# LickStick_v1_0_1.net
KiCad netlist of a schematic drawn in EAGLE
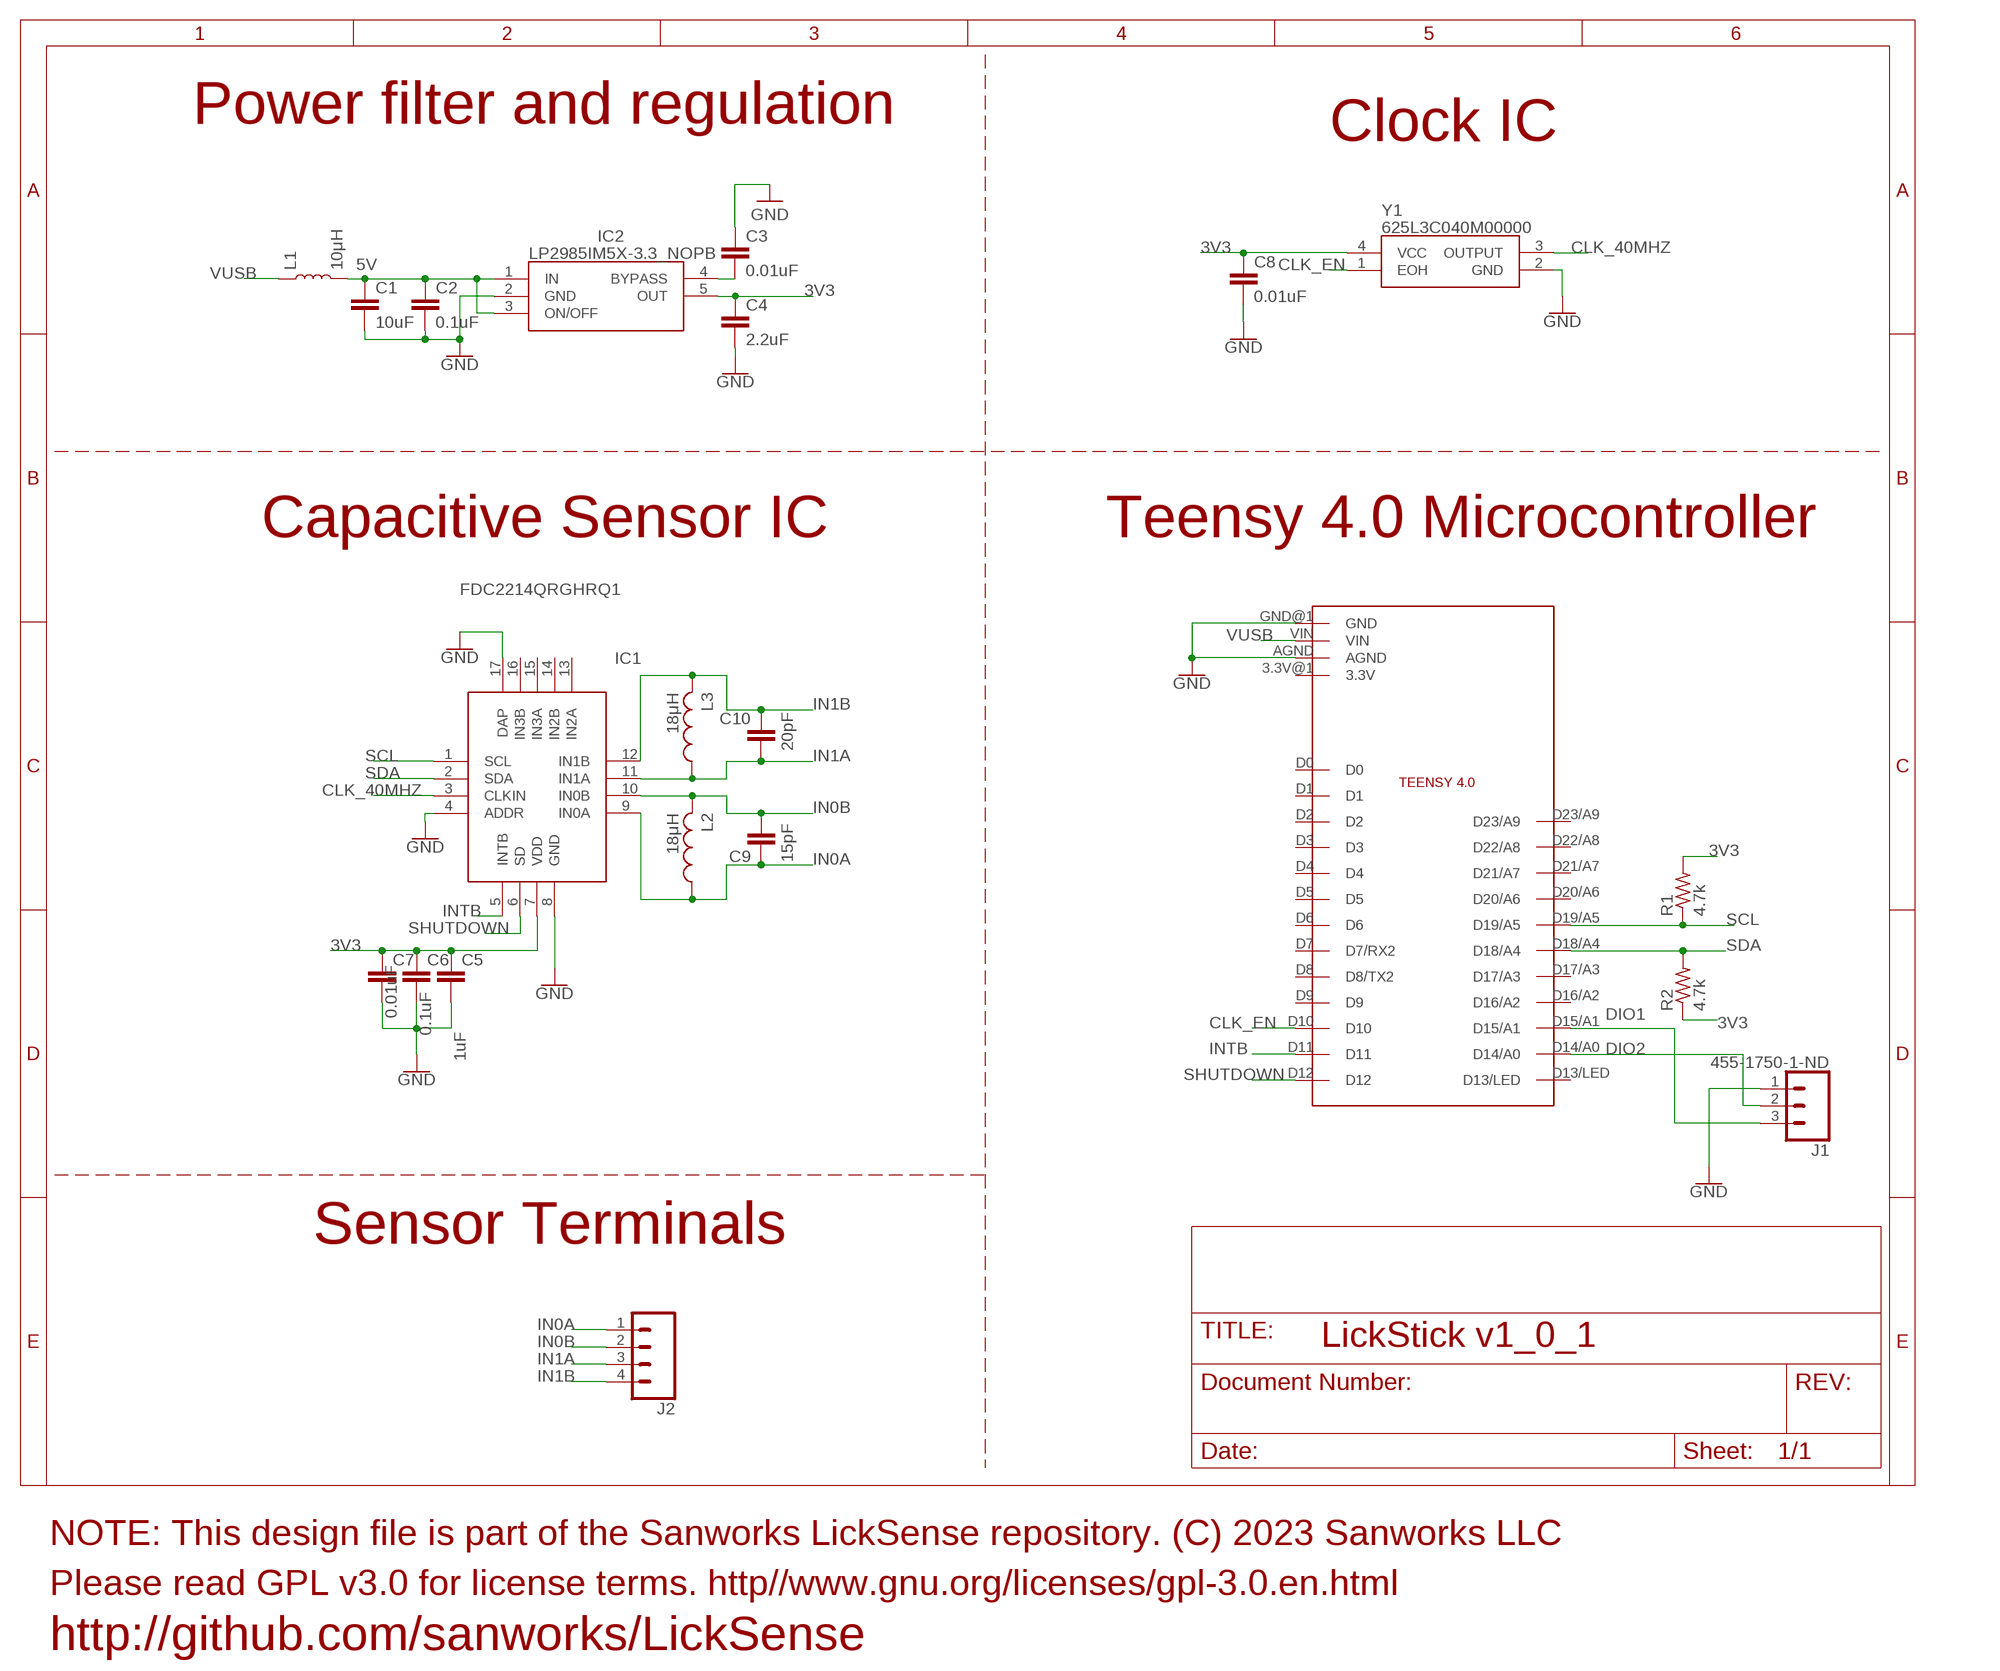
[diagram p0: schematic, sheet 1]

(export (version "E")
  (design (tool "Eeschema 10.0.6"))
  (components
    (comp (ref "C1")
      (value "10uF")
      (footprint "eagle-import:0805")
      (libsource (lib "eagle-import") (part "10UF-0805-10V-10%"))
    )
    (comp (ref "C2")
      (value "0.1uF")
      (footprint "eagle-import:0805")
      (libsource (lib "eagle-import") (part "1.0UF-0805-25V-(+80/-20%)"))
    )
    (comp (ref "C3")
      (value "0.01uF")
      (footprint "eagle-import:0805")
      (libsource (lib "eagle-import") (part "1.0UF-0805-25V-(+80/-20%)"))
    )
    (comp (ref "C4")
      (value "2.2uF")
      (footprint "eagle-import:0805")
      (libsource (lib "eagle-import") (part "1.0UF-0805-25V-(+80/-20%)"))
    )
    (comp (ref "C5")
      (value "1uF")
      (footprint "eagle-import:0805")
      (libsource (lib "eagle-import") (part "1.0UF-0805-25V-(+80/-20%)"))
    )
    (comp (ref "C6")
      (value "0.1uF")
      (footprint "eagle-import:0805")
      (libsource (lib "eagle-import") (part "1.0UF-0805-25V-(+80/-20%)"))
    )
    (comp (ref "C7")
      (value "0.01uF")
      (footprint "eagle-import:0805")
      (libsource (lib "eagle-import") (part "1.0UF-0805-25V-(+80/-20%)"))
    )
    (comp (ref "C8")
      (value "0.01uF")
      (footprint "eagle-import:0805")
      (libsource (lib "eagle-import") (part "1.0UF-0805-25V-(+80/-20%)"))
    )
    (comp (ref "C9")
      (value "15pF")
      (footprint "eagle-import:0805")
      (libsource (lib "eagle-import") (part "1.0UF-0805-25V-(+80/-20%)"))
    )
    (comp (ref "C10")
      (value "20pF")
      (footprint "eagle-import:0805")
      (libsource (lib "eagle-import") (part "1.0UF-0805-25V-(+80/-20%)"))
    )
    (comp (ref "IC1")
      (value "FDC2214QRGHRQ1")
      (footprint "eagle-import:QFN50P400X400X80-17N")
      (fields (field (name "MOUSER_PART_NUMBER") "595-FDC2214QRGHRQ1"))
      (libsource (lib "eagle-import") (part "FDC2214QRGHRQ1"))
    )
    (comp (ref "IC2")
      (value "LP2985IM5X-3.3_NOPB")
      (footprint "eagle-import:SOT95P280X145-5N")
      (fields
        (field (name "MANUFACTURER_PART_NUMBER") "LP2985IM5X-3.3/NOPB")
        (field (name "MOUSER_PART_NUMBER") "926-LP2985IM5X33NOPB")
      )
      (libsource (lib "eagle-import") (part "LP2985IM5X-3.3_NOPB"))
    )
    (comp (ref "J1")
      (value "455-1750-1-ND")
      (footprint "eagle-import:1X03")
      (libsource (lib "eagle-import") (part "CONN_03"))
    )
    (comp (ref "J2")
      (value "CONN_04PTH")
      (footprint "eagle-import:1X04")
      (libsource (lib "eagle-import") (part "CONN_04PTH"))
    )
    (comp (ref "L1")
      (value "10μH")
      (footprint "eagle-import:0806")
      (libsource (lib "eagle-import") (part "2.2μH_SHIELDED_INDUCTOR"))
    )
    (comp (ref "L2")
      (value "18μH")
      (footprint "eagle-import:L3225P")
      (libsource (lib "eagle-import") (part "L-USL3225P"))
    )
    (comp (ref "L3")
      (value "18μH")
      (footprint "eagle-import:L3225P")
      (libsource (lib "eagle-import") (part "L-USL3225P"))
    )
    (comp (ref "MC1")
      (value "TEENSY4.0_SIMPLE_NO_VUSB")
      (footprint "eagle-import:TEENSY4.0_SIMPLE_NO_VUSB")
      (libsource (lib "eagle-import") (part "TEENSY4.0_SIMPLE_NO_VUSB"))
    )
    (comp (ref "R1")
      (value "4.7k")
      (footprint "eagle-import:R0805")
      (libsource (lib "eagle-import") (part "R-US_R0805"))
    )
    (comp (ref "R2")
      (value "4.7k")
      (footprint "eagle-import:R0805")
      (libsource (lib "eagle-import") (part "R-US_R0805"))
    )
    (comp (ref "Y1")
      (value "625L3C040M00000")
      (footprint "eagle-import:625L3C040M00000")
      (fields (field (name "MOUSER_PART_NUMBER") "774-625L3C040M00000"))
      (libsource (lib "eagle-import") (part "625L3C040M00000"))
    )
  )
  (nets
    (net (code "1") (name "/3V3") (class "Default")
      (node (ref "C4") (pin "1") (pinfunction "1_1") (pintype "passive"))
      (node (ref "C5") (pin "1") (pinfunction "1_1") (pintype "passive"))
      (node (ref "C6") (pin "1") (pinfunction "1_1") (pintype "passive"))
      (node (ref "C7") (pin "1") (pinfunction "1_1") (pintype "passive"))
      (node (ref "C8") (pin "1") (pinfunction "1_1") (pintype "passive"))
      (node (ref "IC1") (pin "7") (pinfunction "VDD_7") (pintype "bidirectional"))
      (node (ref "IC2") (pin "5") (pinfunction "OUT_5") (pintype "bidirectional"))
      (node (ref "R1") (pin "2") (pinfunction "2_2") (pintype "passive"))
      (node (ref "R2") (pin "1") (pinfunction "1_1") (pintype "passive"))
      (node (ref "Y1") (pin "4") (pinfunction "VCC_4") (pintype "bidirectional"))
    )
    (net (code "2") (name "/5V") (class "Default")
      (node (ref "C1") (pin "1") (pinfunction "1_1") (pintype "passive"))
      (node (ref "C2") (pin "1") (pinfunction "1_1") (pintype "passive"))
      (node (ref "IC2") (pin "1") (pinfunction "IN_1") (pintype "bidirectional"))
      (node (ref "IC2") (pin "3") (pinfunction "ON/OFF_3") (pintype "bidirectional"))
      (node (ref "L1") (pin "2") (pinfunction "2_2") (pintype "passive"))
    )
    (net (code "3") (name "/CLK_40MHZ") (class "Default")
      (node (ref "IC1") (pin "3") (pinfunction "CLKIN_3") (pintype "bidirectional"))
      (node (ref "Y1") (pin "3") (pinfunction "OUTPUT_3") (pintype "bidirectional"))
    )
    (net (code "4") (name "/CLK_EN") (class "Default")
      (node (ref "MC1") (pin "D10") (pinfunction "D10_D10") (pintype "bidirectional"))
      (node (ref "Y1") (pin "1") (pinfunction "EOH_1") (pintype "bidirectional"))
    )
    (net (code "5") (name "/DIO1") (class "Default")
      (node (ref "J1") (pin "3") (pinfunction "3_3") (pintype "passive"))
      (node (ref "MC1") (pin "D15/A1") (pinfunction "D15/A1_D15/A1") (pintype "bidirectional"))
    )
    (net (code "6") (name "/DIO2") (class "Default")
      (node (ref "J1") (pin "2") (pinfunction "2_2") (pintype "passive"))
      (node (ref "MC1") (pin "D14/A0") (pinfunction "D14/A0_D14/A0") (pintype "bidirectional"))
    )
    (net (code "7") (name "/IN0A") (class "Default")
      (node (ref "C9") (pin "1") (pinfunction "1_1") (pintype "passive"))
      (node (ref "IC1") (pin "9") (pinfunction "IN0A_9") (pintype "bidirectional"))
      (node (ref "J2") (pin "1") (pinfunction "1_1") (pintype "passive"))
      (node (ref "L2") (pin "1") (pinfunction "1_1") (pintype "passive"))
    )
    (net (code "8") (name "/IN0B") (class "Default")
      (node (ref "C9") (pin "2") (pinfunction "2_2") (pintype "passive"))
      (node (ref "IC1") (pin "10") (pinfunction "IN0B_10") (pintype "bidirectional"))
      (node (ref "J2") (pin "2") (pinfunction "2_2") (pintype "passive"))
      (node (ref "L2") (pin "2") (pinfunction "2_2") (pintype "passive"))
    )
    (net (code "9") (name "/IN1A") (class "Default")
      (node (ref "C10") (pin "1") (pinfunction "1_1") (pintype "passive"))
      (node (ref "IC1") (pin "11") (pinfunction "IN1A_11") (pintype "bidirectional"))
      (node (ref "J2") (pin "3") (pinfunction "3_3") (pintype "passive"))
      (node (ref "L3") (pin "1") (pinfunction "1_1") (pintype "passive"))
    )
    (net (code "10") (name "/IN1B") (class "Default")
      (node (ref "C10") (pin "2") (pinfunction "2_2") (pintype "passive"))
      (node (ref "IC1") (pin "12") (pinfunction "IN1B_12") (pintype "bidirectional"))
      (node (ref "J2") (pin "4") (pinfunction "4_4") (pintype "passive"))
      (node (ref "L3") (pin "2") (pinfunction "2_2") (pintype "passive"))
    )
    (net (code "11") (name "/INTB") (class "Default")
      (node (ref "IC1") (pin "5") (pinfunction "INTB_5") (pintype "bidirectional"))
      (node (ref "MC1") (pin "D11") (pinfunction "D11_D11") (pintype "bidirectional"))
    )
    (net (code "12") (name "/SCL") (class "Default")
      (node (ref "IC1") (pin "1") (pinfunction "SCL_1") (pintype "bidirectional"))
      (node (ref "MC1") (pin "D19/A5") (pinfunction "D19/A5_D19/A5") (pintype "bidirectional"))
      (node (ref "R1") (pin "1") (pinfunction "1_1") (pintype "passive"))
    )
    (net (code "13") (name "/SDA") (class "Default")
      (node (ref "IC1") (pin "2") (pinfunction "SDA_2") (pintype "bidirectional"))
      (node (ref "MC1") (pin "D18/A4") (pinfunction "D18/A4_D18/A4") (pintype "bidirectional"))
      (node (ref "R2") (pin "2") (pinfunction "2_2") (pintype "passive"))
    )
    (net (code "14") (name "/SHUTDOWN") (class "Default")
      (node (ref "IC1") (pin "6") (pinfunction "SD_6") (pintype "bidirectional"))
      (node (ref "MC1") (pin "D12") (pinfunction "D12_D12") (pintype "bidirectional"))
    )
    (net (code "15") (name "/VUSB") (class "Default")
      (node (ref "L1") (pin "1") (pinfunction "1_1") (pintype "passive"))
      (node (ref "MC1") (pin "VIN") (pinfunction "VIN_VIN") (pintype "bidirectional"))
    )
    (net (code "16") (name "GND") (class "Default")
      (node (ref "C1") (pin "2") (pinfunction "2_2") (pintype "passive"))
      (node (ref "C2") (pin "2") (pinfunction "2_2") (pintype "passive"))
      (node (ref "C3") (pin "1") (pinfunction "1_1") (pintype "passive"))
      (node (ref "C4") (pin "2") (pinfunction "2_2") (pintype "passive"))
      (node (ref "C5") (pin "2") (pinfunction "2_2") (pintype "passive"))
      (node (ref "C6") (pin "2") (pinfunction "2_2") (pintype "passive"))
      (node (ref "C7") (pin "2") (pinfunction "2_2") (pintype "passive"))
      (node (ref "C8") (pin "2") (pinfunction "2_2") (pintype "passive"))
      (node (ref "IC1") (pin "17") (pinfunction "DAP_17") (pintype "bidirectional"))
      (node (ref "IC1") (pin "4") (pinfunction "ADDR_4") (pintype "bidirectional"))
      (node (ref "IC1") (pin "8") (pinfunction "GND_8") (pintype "bidirectional"))
      (node (ref "IC2") (pin "2") (pinfunction "GND_2") (pintype "bidirectional"))
      (node (ref "J1") (pin "1") (pinfunction "1_1") (pintype "passive"))
      (node (ref "MC1") (pin "AGND") (pinfunction "AGND_AGND") (pintype "bidirectional"))
      (node (ref "MC1") (pin "GND@1") (pinfunction "GND_GND@1") (pintype "bidirectional"))
      (node (ref "Y1") (pin "2") (pinfunction "GND_2") (pintype "bidirectional"))
    )
    (net (code "17") (name "Net-(IC2-BYPASS)") (class "Default")
      (node (ref "C3") (pin "2") (pinfunction "2_2") (pintype "passive"))
      (node (ref "IC2") (pin "4") (pinfunction "BYPASS_4") (pintype "bidirectional"))
    )
    (net (code "18") (name "unconnected-(IC1-IN2A-Pad13)") (class "Default")
      (node (ref "IC1") (pin "13") (pinfunction "IN2A_13") (pintype "bidirectional"))
    )
    (net (code "19") (name "unconnected-(IC1-IN2B-Pad14)") (class "Default")
      (node (ref "IC1") (pin "14") (pinfunction "IN2B_14") (pintype "bidirectional"))
    )
    (net (code "20") (name "unconnected-(IC1-IN3A-Pad15)") (class "Default")
      (node (ref "IC1") (pin "15") (pinfunction "IN3A_15") (pintype "bidirectional"))
    )
    (net (code "21") (name "unconnected-(IC1-IN3B-Pad16)") (class "Default")
      (node (ref "IC1") (pin "16") (pinfunction "IN3B_16") (pintype "bidirectional"))
    )
    (net (code "22") (name "unconnected-(MC1-3.3V-Pad3.3V@1)") (class "Default")
      (node (ref "MC1") (pin "3.3V@1") (pinfunction "3.3V_3.3V@1") (pintype "bidirectional"))
    )
    (net (code "23") (name "unconnected-(MC1-D7{slash}RX2-PadD7)") (class "Default")
      (node (ref "MC1") (pin "D7") (pinfunction "D7/RX2_D7") (pintype "bidirectional"))
    )
    (net (code "24") (name "unconnected-(MC1-D8{slash}TX2-PadD8)") (class "Default")
      (node (ref "MC1") (pin "D8") (pinfunction "D8/TX2_D8") (pintype "bidirectional"))
    )
    (net (code "25") (name "unconnected-(MC1-PadD0)") (class "Default")
      (node (ref "MC1") (pin "D0") (pinfunction "D0_D0") (pintype "bidirectional"))
    )
    (net (code "26") (name "unconnected-(MC1-PadD1)") (class "Default")
      (node (ref "MC1") (pin "D1") (pinfunction "D1_D1") (pintype "bidirectional"))
    )
    (net (code "27") (name "unconnected-(MC1-PadD2)") (class "Default")
      (node (ref "MC1") (pin "D2") (pinfunction "D2_D2") (pintype "bidirectional"))
    )
    (net (code "28") (name "unconnected-(MC1-PadD3)") (class "Default")
      (node (ref "MC1") (pin "D3") (pinfunction "D3_D3") (pintype "bidirectional"))
    )
    (net (code "29") (name "unconnected-(MC1-PadD4)") (class "Default")
      (node (ref "MC1") (pin "D4") (pinfunction "D4_D4") (pintype "bidirectional"))
    )
    (net (code "30") (name "unconnected-(MC1-PadD5)") (class "Default")
      (node (ref "MC1") (pin "D5") (pinfunction "D5_D5") (pintype "bidirectional"))
    )
    (net (code "31") (name "unconnected-(MC1-PadD6)") (class "Default")
      (node (ref "MC1") (pin "D6") (pinfunction "D6_D6") (pintype "bidirectional"))
    )
    (net (code "32") (name "unconnected-(MC1-PadD9)") (class "Default")
      (node (ref "MC1") (pin "D9") (pinfunction "D9_D9") (pintype "bidirectional"))
    )
    (net (code "33") (name "unconnected-(MC1-PadD13{slash}LED)") (class "Default")
      (node (ref "MC1") (pin "D13/LED") (pinfunction "D13/LED_D13/LED") (pintype "bidirectional"))
    )
    (net (code "34") (name "unconnected-(MC1-PadD16{slash}A2)") (class "Default")
      (node (ref "MC1") (pin "D16/A2") (pinfunction "D16/A2_D16/A2") (pintype "bidirectional"))
    )
    (net (code "35") (name "unconnected-(MC1-PadD17{slash}A3)") (class "Default")
      (node (ref "MC1") (pin "D17/A3") (pinfunction "D17/A3_D17/A3") (pintype "bidirectional"))
    )
    (net (code "36") (name "unconnected-(MC1-PadD20{slash}A6)") (class "Default")
      (node (ref "MC1") (pin "D20/A6") (pinfunction "D20/A6_D20/A6") (pintype "bidirectional"))
    )
    (net (code "37") (name "unconnected-(MC1-PadD21{slash}A7)") (class "Default")
      (node (ref "MC1") (pin "D21/A7") (pinfunction "D21/A7_D21/A7") (pintype "bidirectional"))
    )
    (net (code "38") (name "unconnected-(MC1-PadD22{slash}A8)") (class "Default")
      (node (ref "MC1") (pin "D22/A8") (pinfunction "D22/A8_D22/A8") (pintype "bidirectional"))
    )
    (net (code "39") (name "unconnected-(MC1-PadD23{slash}A9)") (class "Default")
      (node (ref "MC1") (pin "D23/A9") (pinfunction "D23/A9_D23/A9") (pintype "bidirectional"))
    )
  )
)
